# Voltage_Regulation.net
KiCad netlist of a schematic drawn in Altium Designer
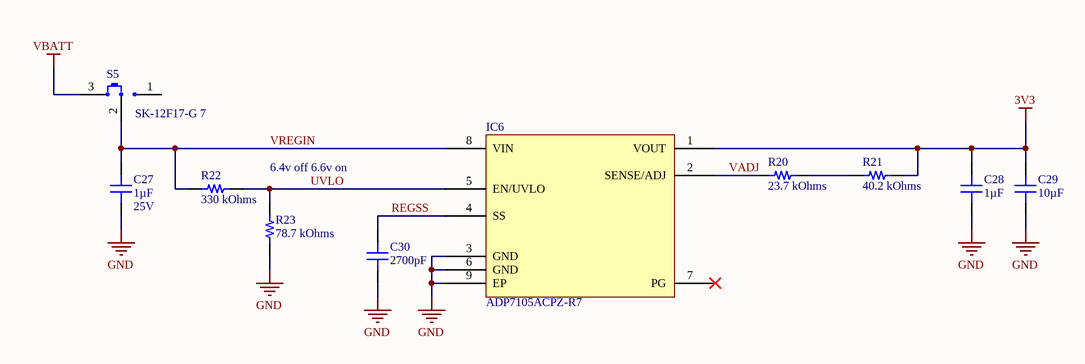
[diagram p0: Voltage Regulation.SchDoc]

(export (version "E")
  (design (tool "Eeschema 10.0.6"))
  (components
    (comp (ref "C27")
      (value "1µF")
      (footprint "CAP 0603_1608")
      (description "CAP CER 1UF 25V X5R 0603")
      (fields
        (field (name "PART NUMBER") "CL10A105KA8NNNC")
        (field (name "MANUFACTURER") "Samsung Electro-Mechanics")
        (field (name "VOLTAGE - RATED") "25V")
      )
      (libsource (lib "altiumlibrary.com") (part "Capacitor"))
    )
    (comp (ref "C28")
      (value "1µF")
      (footprint "CAP 0603_1608")
      (description "CAP CER 1UF 10V X7R 0603")
      (fields (field (name "PART NUMBER") "LMK107B7105KA-T") (field (name "MANUFACTURER") "Taiyo Yuden"))
      (libsource (lib "altiumlibrary.com") (part "Capacitor"))
    )
    (comp (ref "C29")
      (value "10µF")
      (footprint "CAP 0805_2012")
      (description "CAP CER 10UF 10V X5R 0805")
      (fields
        (field (name "PART NUMBER") "CL21A106KPCLQNC")
        (field (name "MANUFACTURER") "Samsung Electro-Mechanics")
      )
      (libsource (lib "altiumlibrary.com") (part "Capacitor"))
    )
    (comp (ref "C30")
      (value "2700pF")
      (footprint "CAP 0603_1608")
      (description "CAP CER 2700PF 50V X7R 0603")
      (fields (field (name "PART NUMBER") "CC0603KRX7R9BB272") (field (name "MANUFACTURER") "Yageo"))
      (libsource (lib "altiumlibrary.com") (part "Capacitor"))
    )
    (comp (ref "IC6")
      (value "ADP7105ACPZ-R7")
      (footprint "AD LFCSP-8 3x3MM CP-8-5")
      (description "IC REG LIN POS ADJ 500MA 8LFCSP")
      (fields (field (name "MANUFACTURER") "Analog Devices Inc."))
      (libsource (lib "altiumlibrary.com") (part "AD ADP7105ACPZ-R2"))
    )
    (comp (ref "R20")
      (value "23.7 kOhms")
      (footprint "RES 0603_1608")
      (description "RES SMD 23.7K OHM 1% 1/10W 0603")
      (fields
        (field (name "PART NUMBER") "ERJ-3EKF2372V")
        (field (name "MANUFACTURER") "Panasonic Electronic Components")
      )
      (libsource (lib "altiumlibrary.com") (part "Resistor"))
    )
    (comp (ref "R21")
      (value "40.2 kOhms")
      (footprint "RES 0603_1608")
      (description "RES SMD 40.2K OHM 1% 1/10W 0603")
      (fields
        (field (name "PART NUMBER") "ERJ-3EKF4022V")
        (field (name "MANUFACTURER") "Panasonic Electronic Components")
      )
      (libsource (lib "altiumlibrary.com") (part "Resistor"))
    )
    (comp (ref "R22")
      (value "330 kOhms")
      (footprint "RES 0603_1608")
      (description "RES SMD 330K OHM 5% 1/4W 0603")
      (fields
        (field (name "PART NUMBER") "ERJ-PA3J334V")
        (field (name "MANUFACTURER") "Panasonic Electronic Components")
      )
      (libsource (lib "altiumlibrary.com") (part "Resistor"))
    )
    (comp (ref "R23")
      (value "78.7 kOhms")
      (footprint "RES 0603_1608")
      (description "RES SMD 78.7K OHM 1% 1/10W 0603")
      (fields
        (field (name "PART NUMBER") "ERJ-3EKF7872V")
        (field (name "MANUFACTURER") "Panasonic Electronic Components")
      )
      (libsource (lib "altiumlibrary.com") (part "Resistor"))
    )
    (comp (ref "S5")
      (value "SK-12F17-G 7")
      (footprint "C&K SK-12F17-G 7")
      (description "SWITCH SLIDE SPDT 300MA 30V")
      (fields (field (name "MANUFACTURER") "C&K"))
      (libsource (lib "altiumlibrary.com") (part "C&K SK-12F17-G 7"))
    )
  )
  (nets
    (net (code "1") (name "/REGSS") (class "Default")
      (node (ref "C30") (pin "2") (pinfunction "2_2") (pintype "passive"))
      (node (ref "IC6") (pin "4") (pinfunction "SS_4") (pintype "passive"))
    )
    (net (code "2") (name "/UVLO") (class "Default")
      (node (ref "IC6") (pin "5") (pinfunction "EN/UVLO_5") (pintype "passive"))
      (node (ref "R22") (pin "2") (pinfunction "2_2") (pintype "passive"))
      (node (ref "R23") (pin "2") (pinfunction "2_2") (pintype "passive"))
    )
    (net (code "3") (name "/VADJ") (class "Default")
      (node (ref "IC6") (pin "2") (pinfunction "SENSE/ADJ_2") (pintype "passive"))
      (node (ref "R20") (pin "1") (pinfunction "1_1") (pintype "passive"))
    )
    (net (code "4") (name "/VREGIN") (class "Default")
      (node (ref "C27") (pin "1") (pinfunction "1_1") (pintype "passive"))
      (node (ref "IC6") (pin "8") (pinfunction "VIN_8") (pintype "passive"))
      (node (ref "R22") (pin "1") (pinfunction "1_1") (pintype "passive"))
      (node (ref "S5") (pin "2") (pinfunction "COM_2") (pintype "passive"))
    )
    (net (code "5") (name "3V3") (class "Default")
      (node (ref "C28") (pin "2") (pinfunction "2_2") (pintype "passive"))
      (node (ref "C29") (pin "2") (pinfunction "2_2") (pintype "passive"))
      (node (ref "IC6") (pin "1") (pinfunction "VOUT_1") (pintype "passive"))
      (node (ref "R21") (pin "1") (pinfunction "1_1") (pintype "passive"))
    )
    (net (code "6") (name "GND") (class "Default")
      (node (ref "C27") (pin "2") (pinfunction "2_2") (pintype "passive"))
      (node (ref "C28") (pin "1") (pinfunction "1_1") (pintype "passive"))
      (node (ref "C29") (pin "1") (pinfunction "1_1") (pintype "passive"))
      (node (ref "C30") (pin "1") (pinfunction "1_1") (pintype "passive"))
      (node (ref "IC6") (pin "3") (pinfunction "GND_3") (pintype "passive"))
      (node (ref "IC6") (pin "6") (pinfunction "GND_6") (pintype "passive"))
      (node (ref "IC6") (pin "9") (pinfunction "EP_9") (pintype "passive"))
      (node (ref "R23") (pin "1") (pinfunction "1_1") (pintype "passive"))
    )
    (net (code "7") (name "Net-(R20-Pad2)") (class "Default")
      (node (ref "R20") (pin "2") (pinfunction "2_2") (pintype "passive"))
      (node (ref "R21") (pin "2") (pinfunction "2_2") (pintype "passive"))
    )
    (net (code "8") (name "VBATT") (class "Default")
      (node (ref "S5") (pin "3") (pinfunction "3_3") (pintype "passive"))
    )
    (net (code "9") (name "unconnected-(IC6-PG-Pad7)") (class "Default")
      (node (ref "IC6") (pin "7") (pinfunction "PG_7") (pintype "passive+no_connect"))
    )
    (net (code "10") (name "unconnected-(S5-Pad1)") (class "Default")
      (node (ref "S5") (pin "1") (pinfunction "1_1") (pintype "passive"))
    )
  )
)
